# lm27313_5_12.net
KiCad netlist of a schematic drawn in Altium Designer
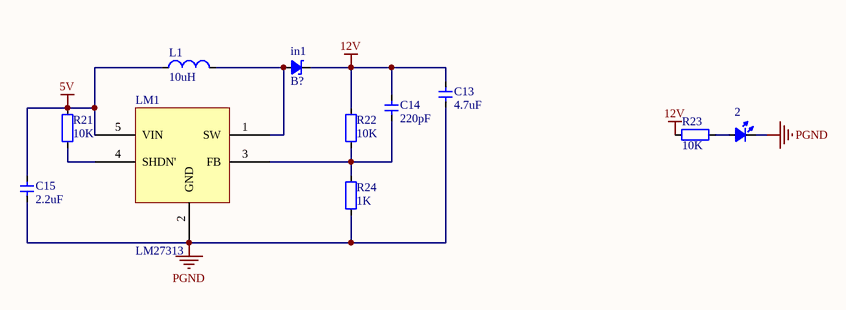
[diagram p0: lm27313_5_12.SchDoc]

(export (version "E")
  (design (tool "Eeschema 10.0.6"))
  (components
    (comp (ref "2")
      (value "LED_0805")
      (footprint "LED_0805_GREEN")
      (description "LED")
      (libsource (lib "SCH_Active") (part "LED_0603"))
    )
    (comp (ref "C13")
      (value "4.7uF")
      (footprint "CAP_0603")
      (description "Capacitor")
      (fields (field (name "Comment") "Cap_0603"))
      (libsource (lib "Integrated_Library") (part "Cap_0603"))
    )
    (comp (ref "C14")
      (value "220pF")
      (footprint "CAP_0603")
      (description "Capacitor")
      (fields (field (name "Comment") "Cap_0603"))
      (libsource (lib "Integrated_Library") (part "Cap_0603"))
    )
    (comp (ref "C15")
      (value "2.2uF")
      (footprint "CAP_0603")
      (description "Capacitor")
      (fields (field (name "Comment") "Cap_0603"))
      (libsource (lib "Integrated_Library") (part "Cap_0603"))
    )
    (comp (ref "in1")
      (value "B?")
      (footprint "PCB_ActiveDIO:SOD-123")
      (description "Diode")
      (fields (field (name "Comment") "SchottkyDiode_SOD123"))
      (libsource (lib "SCH_Active") (part "SchottkyDiode_SOD123"))
    )
    (comp (ref "L1")
      (value "10uH")
      (footprint "indmm5x2_2_2")
      (description "Inductor")
      (libsource (lib "Integrated_Library") (part "Ind_0603"))
    )
    (comp (ref "LM1")
      (value "LM27313")
      (footprint "SOT23-5")
      (libsource (lib "Integrated_Library") (part "LM27313"))
    )
    (comp (ref "R21")
      (value "10K")
      (footprint "RES_0603")
      (description "Resistor")
      (fields (field (name "Comment") "Res_0603"))
      (libsource (lib "") (part "Res_0603_1"))
    )
    (comp (ref "R22")
      (value "10K")
      (footprint "RES_0603")
      (description "Resistor")
      (fields (field (name "Comment") "Res_0603"))
      (libsource (lib "") (part "Res_0603_1"))
    )
    (comp (ref "R23")
      (value "10K")
      (footprint "RES_0603")
      (description "Resistor")
      (fields (field (name "Comment") "Res_0603"))
      (libsource (lib "Integrated_Library") (part "Res_0603"))
    )
    (comp (ref "R24")
      (value "1K")
      (footprint "RES_0603")
      (description "Resistor")
      (fields (field (name "Comment") "Res_0603"))
      (libsource (lib "") (part "Res_0603_1"))
    )
  )
  (nets
    (net (code "1") (name "5V") (class "Default")
      (node (ref "C15") (pin "2") (pinfunction "2_2") (pintype "passive"))
      (node (ref "L1") (pin "1") (pinfunction "1_1") (pintype "passive"))
      (node (ref "LM1") (pin "5") (pinfunction "VIN_5") (pintype "passive"))
      (node (ref "R21") (pin "2") (pinfunction "2_2") (pintype "passive"))
    )
    (net (code "2") (name "12V") (class "Default")
      (node (ref "C13") (pin "2") (pinfunction "2_2") (pintype "passive"))
      (node (ref "C14") (pin "2") (pinfunction "2_2") (pintype "passive"))
      (node (ref "R22") (pin "2") (pinfunction "2_2") (pintype "passive"))
      (node (ref "R23") (pin "1") (pinfunction "1_1") (pintype "passive"))
      (node (ref "in1") (pin "2") (pinfunction "K_2") (pintype "passive"))
    )
    (net (code "3") (name "Net-(2-A)") (class "Default")
      (node (ref "2") (pin "1") (pinfunction "A_1") (pintype "passive"))
      (node (ref "R23") (pin "2") (pinfunction "2_2") (pintype "passive"))
    )
    (net (code "4") (name "Net-(LM1-FB)") (class "Default")
      (node (ref "C14") (pin "1") (pinfunction "1_1") (pintype "passive"))
      (node (ref "LM1") (pin "3") (pinfunction "FB_3") (pintype "passive"))
      (node (ref "R22") (pin "1") (pinfunction "1_1") (pintype "passive"))
      (node (ref "R24") (pin "2") (pinfunction "2_2") (pintype "passive"))
    )
    (net (code "5") (name "Net-(LM1-SHDN')") (class "Default")
      (node (ref "LM1") (pin "4") (pinfunction "SHDN'_4") (pintype "passive"))
      (node (ref "R21") (pin "1") (pinfunction "1_1") (pintype "passive"))
    )
    (net (code "6") (name "Net-(LM1-SW)") (class "Default")
      (node (ref "L1") (pin "2") (pinfunction "2_2") (pintype "passive"))
      (node (ref "LM1") (pin "1") (pinfunction "SW_1") (pintype "passive"))
      (node (ref "in1") (pin "1") (pinfunction "A_1") (pintype "passive"))
    )
    (net (code "7") (name "PGND") (class "Default")
      (node (ref "2") (pin "2") (pinfunction "K_2") (pintype "passive"))
      (node (ref "C13") (pin "1") (pinfunction "1_1") (pintype "passive"))
      (node (ref "C15") (pin "1") (pinfunction "1_1") (pintype "passive"))
      (node (ref "LM1") (pin "2") (pinfunction "GND_2") (pintype "passive"))
      (node (ref "R24") (pin "1") (pinfunction "1_1") (pintype "passive"))
    )
  )
)
